# main.net
KiCad netlist of a schematic drawn in EAGLE
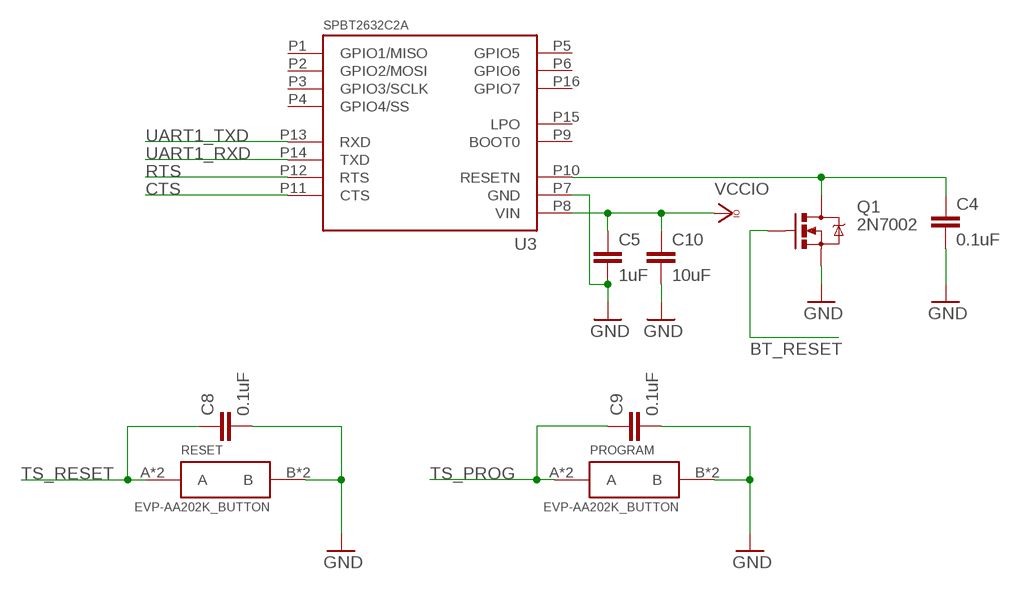
[diagram p0: schematic, sheet 1]
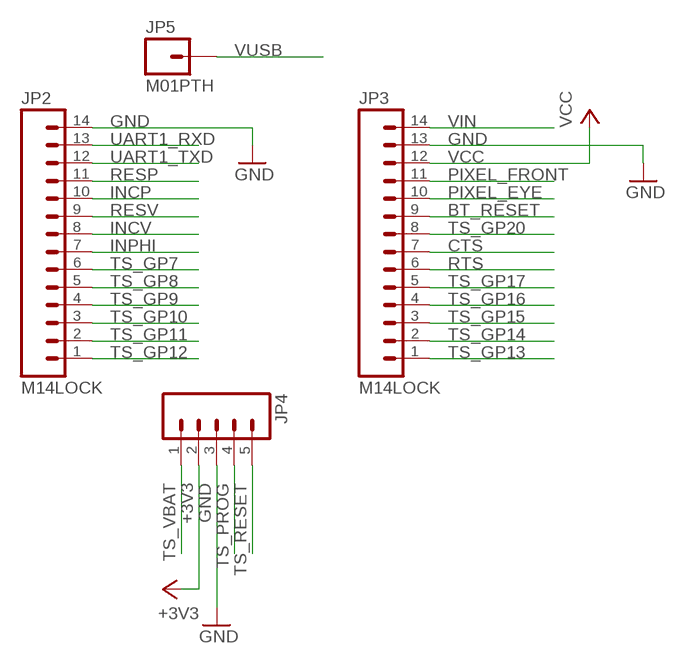
[diagram p1: schematic, sheet 2]
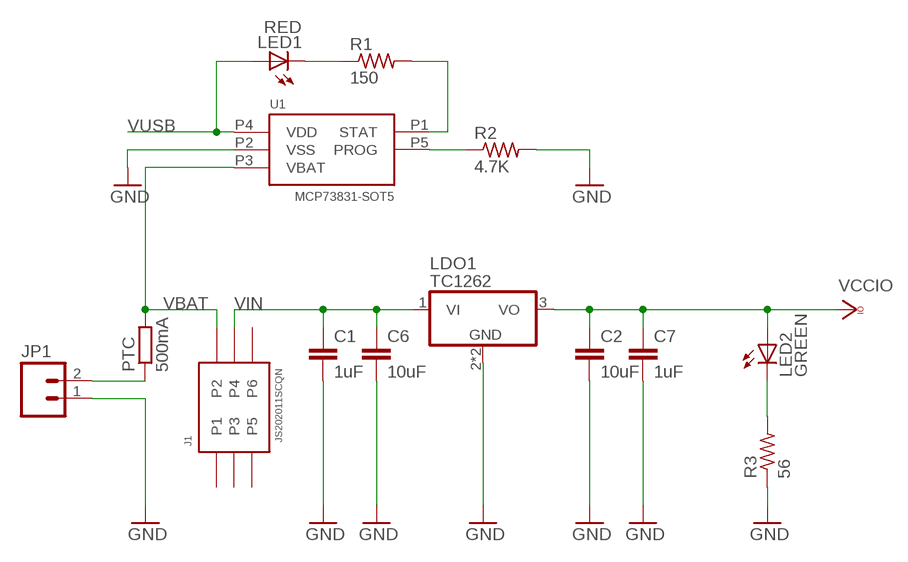
[diagram p2: schematic, sheet 3]

(export (version "E")
  (design (tool "Eeschema 10.0.6"))
  (components
    (comp (ref "JP2")
      (value "M14LOCK")
      (footprint "eagle-import:1X14_LOCK")
      (libsource (lib "eagle-import") (part "M14LOCK"))
    )
    (comp (ref "JP3")
      (value "M14LOCK")
      (footprint "eagle-import:1X14_LOCK")
      (libsource (lib "eagle-import") (part "M14LOCK"))
    )
    (comp (ref "JP4")
      (value "M05LOCK")
      (footprint "eagle-import:1X05_LOCK")
      (libsource (lib "eagle-import") (part "M05LOCK"))
    )
    (comp (ref "JP5")
      (value "M01PTH")
      (footprint "eagle-import:1X01")
      (libsource (lib "eagle-import") (part "M01PTH"))
    )
    (comp (ref "C4")
      (value "0.1uF")
      (footprint "eagle-import:C0402")
      (libsource (lib "eagle-import") (part "resistor_C-EUC0402"))
    )
    (comp (ref "C5")
      (value "1uF")
      (footprint "eagle-import:C0402")
      (libsource (lib "eagle-import") (part "resistor_C-EUC0402"))
    )
    (comp (ref "C8")
      (value "0.1uF")
      (footprint "eagle-import:C0603")
      (libsource (lib "eagle-import") (part "C-EUC0603"))
    )
    (comp (ref "C9")
      (value "0.1uF")
      (footprint "eagle-import:C0603")
      (libsource (lib "eagle-import") (part "C-EUC0603"))
    )
    (comp (ref "C10")
      (value "10uF")
      (footprint "eagle-import:C0603@1")
      (libsource (lib "eagle-import") (part "resistor_C-EUC0603"))
    )
    (comp (ref "PROGRAM")
      (value "EVP-AA202K_BUTTON")
      (footprint "eagle-import:EVP-AA202K_4PIN")
      (libsource (lib "eagle-import") (part "EVP-AA202K_BUTTON"))
    )
    (comp (ref "Q1")
      (value "2N7002")
      (footprint "eagle-import:SOT23-3")
      (libsource (lib "eagle-import") (part "MOSFET-NCHANNELSMD"))
    )
    (comp (ref "RESET")
      (value "EVP-AA202K_BUTTON")
      (footprint "eagle-import:EVP-AA202K_4PIN")
      (libsource (lib "eagle-import") (part "EVP-AA202K_BUTTON"))
    )
    (comp (ref "U3")
      (value "SPBT2632C2A")
      (footprint "eagle-import:SPBT2632C2A_16PIN_SMD")
      (libsource (lib "eagle-import") (part "SPBT2632C2A"))
    )
    (comp (ref "C1")
      (value "1uF")
      (footprint "eagle-import:C0603")
      (libsource (lib "eagle-import") (part "C-EUC0603"))
    )
    (comp (ref "C2")
      (value "10uF")
      (footprint "eagle-import:C0603")
      (libsource (lib "eagle-import") (part "C-EUC0603"))
    )
    (comp (ref "C6")
      (value "10uF")
      (footprint "eagle-import:C0603@1")
      (libsource (lib "eagle-import") (part "resistor_C-EUC0603"))
    )
    (comp (ref "C7")
      (value "1uF")
      (footprint "eagle-import:C0603@1")
      (libsource (lib "eagle-import") (part "resistor_C-EUC0603"))
    )
    (comp (ref "J1")
      (value "JS202011SCQN")
      (footprint "eagle-import:JS2020_6PIN_SMT")
      (libsource (lib "eagle-import") (part "JS202011SCQN"))
    )
    (comp (ref "JP1")
      (value "M02-JST-2MM-SMT")
      (footprint "eagle-import:JST-2-SMD")
      (libsource (lib "eagle-import") (part "M02-JST-2MM-SMT"))
    )
    (comp (ref "LDO1")
      (value "TC1262")
      (footprint "eagle-import:SOT223")
      (libsource (lib "eagle-import") (part "MCP1703DB"))
    )
    (comp (ref "LED1")
      (value "RED")
      (footprint "eagle-import:CHIPLED_0603")
      (libsource (lib "eagle-import") (part "LEDCHIPLED_0603"))
    )
    (comp (ref "LED2")
      (value "GREEN")
      (footprint "eagle-import:CHIPLED_0603")
      (libsource (lib "eagle-import") (part "LEDCHIPLED_0603"))
    )
    (comp (ref "PTC")
      (value "500mA")
      (footprint "eagle-import:R0402")
      (libsource (lib "eagle-import") (part "R-EU_R0402"))
    )
    (comp (ref "R1")
      (value "150")
      (footprint "eagle-import:R0402")
      (libsource (lib "eagle-import") (part "resistor_R-US_R0402"))
    )
    (comp (ref "R2")
      (value "4.7K")
      (footprint "eagle-import:R0402")
      (libsource (lib "eagle-import") (part "resistor_R-US_R0402"))
    )
    (comp (ref "R3")
      (value "56")
      (footprint "eagle-import:R0603")
      (libsource (lib "eagle-import") (part "R-US_R0603"))
    )
    (comp (ref "U1")
      (value "MCP73831-SOT5")
      (footprint "eagle-import:SOT23-5")
      (libsource (lib "eagle-import") (part "MCP73831-SOT5"))
    )
  )
  (nets
    (net (code "1") (name "+3V3") (class "Default")
      (node (ref "JP4") (pin "2") (pinfunction "2_2") (pintype "passive"))
    )
    (net (code "2") (name "BT_RESET") (class "Default")
      (node (ref "JP3") (pin "9") (pinfunction "9_9") (pintype "passive"))
      (node (ref "Q1") (pin "1") (pinfunction "G_1") (pintype "passive"))
    )
    (net (code "3") (name "CTS") (class "Default")
      (node (ref "JP3") (pin "7") (pinfunction "7_7") (pintype "passive"))
      (node (ref "U3") (pin "P11") (pinfunction "CTS_P11") (pintype "bidirectional"))
    )
    (net (code "4") (name "GND") (class "Default")
      (node (ref "C1") (pin "2") (pinfunction "2_2") (pintype "passive"))
      (node (ref "C10") (pin "2") (pinfunction "2_2") (pintype "passive"))
      (node (ref "C2") (pin "2") (pinfunction "2_2") (pintype "passive"))
      (node (ref "C4") (pin "2") (pinfunction "2_2") (pintype "passive"))
      (node (ref "C5") (pin "2") (pinfunction "2_2") (pintype "passive"))
      (node (ref "C6") (pin "2") (pinfunction "2_2") (pintype "passive"))
      (node (ref "C7") (pin "2") (pinfunction "2_2") (pintype "passive"))
      (node (ref "C8") (pin "2") (pinfunction "2_2") (pintype "passive"))
      (node (ref "C9") (pin "2") (pinfunction "2_2") (pintype "passive"))
      (node (ref "JP1") (pin "1") (pinfunction "1_1") (pintype "passive"))
      (node (ref "JP2") (pin "14") (pinfunction "14_14") (pintype "passive"))
      (node (ref "JP3") (pin "13") (pinfunction "13_13") (pintype "passive"))
      (node (ref "JP4") (pin "3") (pinfunction "3_3") (pintype "passive"))
      (node (ref "LDO1") (pin "2") (pinfunction "GND_2") (pintype "passive"))
      (node (ref "LDO1") (pin "4") (pinfunction "GND_4") (pintype "passive"))
      (node (ref "PROGRAM") (pin "B") (pinfunction "B_B") (pintype "bidirectional"))
      (node (ref "PROGRAM") (pin "B'") (pinfunction "B_B'") (pintype "bidirectional"))
      (node (ref "Q1") (pin "2") (pinfunction "S_2") (pintype "passive"))
      (node (ref "R2") (pin "2") (pinfunction "2_2") (pintype "passive"))
      (node (ref "R3") (pin "1") (pinfunction "1_1") (pintype "passive"))
      (node (ref "RESET") (pin "B") (pinfunction "B_B") (pintype "bidirectional"))
      (node (ref "RESET") (pin "B'") (pinfunction "B_B'") (pintype "bidirectional"))
      (node (ref "U1") (pin "P2") (pinfunction "VSS_P2") (pintype "bidirectional"))
      (node (ref "U3") (pin "P7") (pinfunction "GND_P7") (pintype "bidirectional"))
    )
    (net (code "5") (name "INCP") (class "Default")
      (node (ref "JP2") (pin "10") (pinfunction "10_10") (pintype "passive"))
    )
    (net (code "6") (name "INCV") (class "Default")
      (node (ref "JP2") (pin "8") (pinfunction "8_8") (pintype "passive"))
    )
    (net (code "7") (name "INPHI") (class "Default")
      (node (ref "JP2") (pin "7") (pinfunction "7_7") (pintype "passive"))
    )
    (net (code "8") (name "Net-(JP1-Pad2)") (class "Default")
      (node (ref "JP1") (pin "2") (pinfunction "2_2") (pintype "passive"))
      (node (ref "PTC") (pin "1") (pinfunction "1_1") (pintype "passive"))
    )
    (net (code "9") (name "Net-(LED1-PadC)") (class "Default")
      (node (ref "LED1") (pin "C") (pinfunction "C_C") (pintype "passive"))
      (node (ref "R1") (pin "1") (pinfunction "1_1") (pintype "passive"))
    )
    (net (code "10") (name "Net-(LED2-PadC)") (class "Default")
      (node (ref "LED2") (pin "C") (pinfunction "C_C") (pintype "passive"))
      (node (ref "R3") (pin "2") (pinfunction "2_2") (pintype "passive"))
    )
    (net (code "11") (name "Net-(Q1-D)") (class "Default")
      (node (ref "C4") (pin "1") (pinfunction "1_1") (pintype "passive"))
      (node (ref "Q1") (pin "3") (pinfunction "D_3") (pintype "passive"))
      (node (ref "U3") (pin "P10") (pinfunction "RESETN_P10") (pintype "bidirectional"))
    )
    (net (code "12") (name "Net-(U1-PROG)") (class "Default")
      (node (ref "R2") (pin "1") (pinfunction "1_1") (pintype "passive"))
      (node (ref "U1") (pin "P5") (pinfunction "PROG_P5") (pintype "bidirectional"))
    )
    (net (code "13") (name "Net-(U1-STAT)") (class "Default")
      (node (ref "R1") (pin "2") (pinfunction "2_2") (pintype "passive"))
      (node (ref "U1") (pin "P1") (pinfunction "STAT_P1") (pintype "bidirectional"))
    )
    (net (code "14") (name "PIXEL_EYE") (class "Default")
      (node (ref "JP3") (pin "10") (pinfunction "10_10") (pintype "passive"))
    )
    (net (code "15") (name "PIXEL_FRONT") (class "Default")
      (node (ref "JP3") (pin "11") (pinfunction "11_11") (pintype "passive"))
    )
    (net (code "16") (name "RESP") (class "Default")
      (node (ref "JP2") (pin "11") (pinfunction "11_11") (pintype "passive"))
    )
    (net (code "17") (name "RESV") (class "Default")
      (node (ref "JP2") (pin "9") (pinfunction "9_9") (pintype "passive"))
    )
    (net (code "18") (name "RTS") (class "Default")
      (node (ref "JP3") (pin "6") (pinfunction "6_6") (pintype "passive"))
      (node (ref "U3") (pin "P12") (pinfunction "RTS_P12") (pintype "bidirectional"))
    )
    (net (code "19") (name "TS_GP7") (class "Default")
      (node (ref "JP2") (pin "6") (pinfunction "6_6") (pintype "passive"))
    )
    (net (code "20") (name "TS_GP8") (class "Default")
      (node (ref "JP2") (pin "5") (pinfunction "5_5") (pintype "passive"))
    )
    (net (code "21") (name "TS_GP9") (class "Default")
      (node (ref "JP2") (pin "4") (pinfunction "4_4") (pintype "passive"))
    )
    (net (code "22") (name "TS_GP10") (class "Default")
      (node (ref "JP2") (pin "3") (pinfunction "3_3") (pintype "passive"))
    )
    (net (code "23") (name "TS_GP11") (class "Default")
      (node (ref "JP2") (pin "2") (pinfunction "2_2") (pintype "passive"))
    )
    (net (code "24") (name "TS_GP12") (class "Default")
      (node (ref "JP2") (pin "1") (pinfunction "1_1") (pintype "passive"))
    )
    (net (code "25") (name "TS_GP13") (class "Default")
      (node (ref "JP3") (pin "1") (pinfunction "1_1") (pintype "passive"))
    )
    (net (code "26") (name "TS_GP14") (class "Default")
      (node (ref "JP3") (pin "2") (pinfunction "2_2") (pintype "passive"))
    )
    (net (code "27") (name "TS_GP15") (class "Default")
      (node (ref "JP3") (pin "3") (pinfunction "3_3") (pintype "passive"))
    )
    (net (code "28") (name "TS_GP16") (class "Default")
      (node (ref "JP3") (pin "4") (pinfunction "4_4") (pintype "passive"))
    )
    (net (code "29") (name "TS_GP17") (class "Default")
      (node (ref "JP3") (pin "5") (pinfunction "5_5") (pintype "passive"))
    )
    (net (code "30") (name "TS_GP20") (class "Default")
      (node (ref "JP3") (pin "8") (pinfunction "8_8") (pintype "passive"))
    )
    (net (code "31") (name "TS_PROG") (class "Default")
      (node (ref "C9") (pin "1") (pinfunction "1_1") (pintype "passive"))
      (node (ref "JP4") (pin "4") (pinfunction "4_4") (pintype "passive"))
      (node (ref "PROGRAM") (pin "A") (pinfunction "A_A") (pintype "bidirectional"))
      (node (ref "PROGRAM") (pin "A'") (pinfunction "A_A'") (pintype "bidirectional"))
    )
    (net (code "32") (name "TS_RESET") (class "Default")
      (node (ref "C8") (pin "1") (pinfunction "1_1") (pintype "passive"))
      (node (ref "JP4") (pin "5") (pinfunction "5_5") (pintype "passive"))
      (node (ref "RESET") (pin "A") (pinfunction "A_A") (pintype "bidirectional"))
      (node (ref "RESET") (pin "A'") (pinfunction "A_A'") (pintype "bidirectional"))
    )
    (net (code "33") (name "TS_VBAT") (class "Default")
      (node (ref "JP4") (pin "1") (pinfunction "1_1") (pintype "passive"))
    )
    (net (code "34") (name "UART1_RXD") (class "Default")
      (node (ref "JP2") (pin "13") (pinfunction "13_13") (pintype "passive"))
      (node (ref "U3") (pin "P14") (pinfunction "TXD_P14") (pintype "bidirectional"))
    )
    (net (code "35") (name "UART1_TXD") (class "Default")
      (node (ref "JP2") (pin "12") (pinfunction "12_12") (pintype "passive"))
      (node (ref "U3") (pin "P13") (pinfunction "RXD_P13") (pintype "bidirectional"))
    )
    (net (code "36") (name "VBAT") (class "Default")
      (node (ref "J1") (pin "P2") (pinfunction "P2_P2") (pintype "bidirectional"))
      (node (ref "PTC") (pin "2") (pinfunction "2_2") (pintype "passive"))
      (node (ref "U1") (pin "P3") (pinfunction "VBAT_P3") (pintype "bidirectional"))
    )
    (net (code "37") (name "VCC") (class "Default")
      (node (ref "JP3") (pin "12") (pinfunction "12_12") (pintype "passive"))
    )
    (net (code "38") (name "VCCIO") (class "Default")
      (node (ref "C10") (pin "1") (pinfunction "1_1") (pintype "passive"))
      (node (ref "C2") (pin "1") (pinfunction "1_1") (pintype "passive"))
      (node (ref "C5") (pin "1") (pinfunction "1_1") (pintype "passive"))
      (node (ref "C7") (pin "1") (pinfunction "1_1") (pintype "passive"))
      (node (ref "LDO1") (pin "3") (pinfunction "VO_3") (pintype "passive"))
      (node (ref "LED2") (pin "A") (pinfunction "A_A") (pintype "passive"))
      (node (ref "U3") (pin "P8") (pinfunction "VIN_P8") (pintype "bidirectional"))
    )
    (net (code "39") (name "VIN") (class "Default")
      (node (ref "C1") (pin "1") (pinfunction "1_1") (pintype "passive"))
      (node (ref "C6") (pin "1") (pinfunction "1_1") (pintype "passive"))
      (node (ref "J1") (pin "P4") (pinfunction "P4_P4") (pintype "bidirectional"))
      (node (ref "JP3") (pin "14") (pinfunction "14_14") (pintype "passive"))
      (node (ref "LDO1") (pin "1") (pinfunction "VI_1") (pintype "input"))
    )
    (net (code "40") (name "VUSB") (class "Default")
      (node (ref "JP5") (pin "1") (pinfunction "1_1") (pintype "passive"))
      (node (ref "LED1") (pin "A") (pinfunction "A_A") (pintype "passive"))
      (node (ref "U1") (pin "P4") (pinfunction "VDD_P4") (pintype "bidirectional"))
    )
    (net (code "41") (name "unconnected-(J1-PadP1)") (class "Default")
      (node (ref "J1") (pin "P1") (pinfunction "P1_P1") (pintype "bidirectional"))
    )
    (net (code "42") (name "unconnected-(J1-PadP3)") (class "Default")
      (node (ref "J1") (pin "P3") (pinfunction "P3_P3") (pintype "bidirectional"))
    )
    (net (code "43") (name "unconnected-(J1-PadP5)") (class "Default")
      (node (ref "J1") (pin "P5") (pinfunction "P5_P5") (pintype "bidirectional"))
    )
    (net (code "44") (name "unconnected-(J1-PadP6)") (class "Default")
      (node (ref "J1") (pin "P6") (pinfunction "P6_P6") (pintype "bidirectional"))
    )
    (net (code "45") (name "unconnected-(U3-BOOT0-PadP9)") (class "Default")
      (node (ref "U3") (pin "P9") (pinfunction "BOOT0_P9") (pintype "bidirectional"))
    )
    (net (code "46") (name "unconnected-(U3-GPIO1{slash}MISO-PadP1)") (class "Default")
      (node (ref "U3") (pin "P1") (pinfunction "GPIO1/MISO_P1") (pintype "bidirectional"))
    )
    (net (code "47") (name "unconnected-(U3-GPIO2{slash}MOSI-PadP2)") (class "Default")
      (node (ref "U3") (pin "P2") (pinfunction "GPIO2/MOSI_P2") (pintype "bidirectional"))
    )
    (net (code "48") (name "unconnected-(U3-GPIO3{slash}SCLK-PadP3)") (class "Default")
      (node (ref "U3") (pin "P3") (pinfunction "GPIO3/SCLK_P3") (pintype "bidirectional"))
    )
    (net (code "49") (name "unconnected-(U3-GPIO4{slash}SS-PadP4)") (class "Default")
      (node (ref "U3") (pin "P4") (pinfunction "GPIO4/SS_P4") (pintype "bidirectional"))
    )
    (net (code "50") (name "unconnected-(U3-GPIO5-PadP5)") (class "Default")
      (node (ref "U3") (pin "P5") (pinfunction "GPIO5_P5") (pintype "bidirectional"))
    )
    (net (code "51") (name "unconnected-(U3-GPIO6-PadP6)") (class "Default")
      (node (ref "U3") (pin "P6") (pinfunction "GPIO6_P6") (pintype "bidirectional"))
    )
    (net (code "52") (name "unconnected-(U3-GPIO7-PadP16)") (class "Default")
      (node (ref "U3") (pin "P16") (pinfunction "GPIO7_P16") (pintype "bidirectional"))
    )
    (net (code "53") (name "unconnected-(U3-LPO-PadP15)") (class "Default")
      (node (ref "U3") (pin "P15") (pinfunction "LPO_P15") (pintype "bidirectional"))
    )
  )
)
